# Power_Distribution.net
KiCad netlist of a schematic drawn in Altium Designer
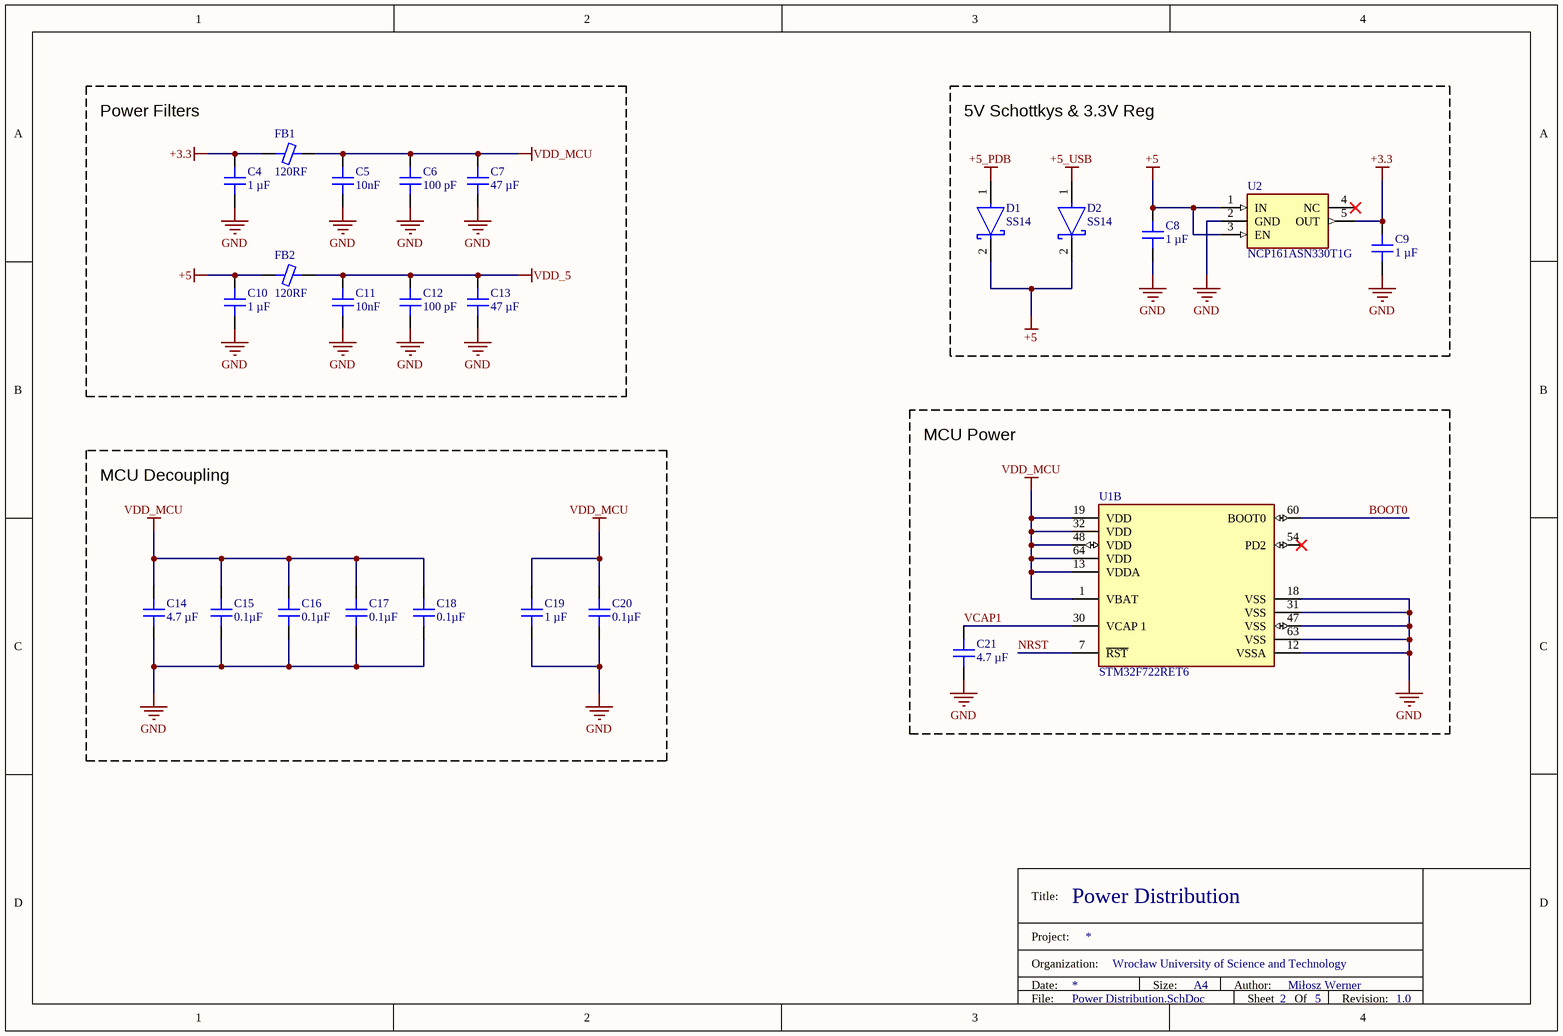
[diagram p0: Power Distribution.SchDoc]

(export (version "E")
  (design (tool "Eeschema 10.0.6"))
  (components
    (comp (ref "C4")
      (value "1 µF")
      (footprint "CAP 0603_1608")
      (description "CAP CER 1UF 25V X5R 0603")
      (fields
        (field (name "PART NUMBER") "CL10A105KA8NFNC")
        (field (name "MANUFACTURER") "Samsung Electro-Mechanics")
      )
      (libsource (lib "Celestial Altium Library - altium_library") (part "Capacitor"))
    )
    (comp (ref "C5")
      (value "10nF")
      (footprint "CAP 0603_1608")
      (description "CAP CER 10000PF 25V X7R 0603")
      (fields (field (name "PART NUMBER") "06033C103KAT2A") (field (name "MANUFACTURER") "AVX Corporation"))
      (libsource (lib "Celestial Altium Library - altium_library") (part "Capacitor"))
    )
    (comp (ref "C6")
      (value "100 pF")
      (footprint "CAP 0603_1608")
      (description "CAP CER 100PF 10V X7R 0603")
      (fields (field (name "PART NUMBER") "C0603C101K8RAC7867") (field (name "MANUFACTURER") "KEMET"))
      (libsource (lib "Celestial Altium Library - altium_library") (part "Capacitor"))
    )
    (comp (ref "C7")
      (value "47 µF")
      (footprint "CAP 0603_1608")
      (description "CAP CER 47UF 6.3V X5R 0603")
      (fields
        (field (name "PART NUMBER") "GRM188R60J476ME15D")
        (field (name "MANUFACTURER") "Murata Electronics")
      )
      (libsource (lib "Celestial Altium Library - altium_library") (part "Capacitor"))
    )
    (comp (ref "C8")
      (value "1 µF")
      (footprint "CAP 0603_1608")
      (description "CAP CER 1UF 25V X5R 0603")
      (fields
        (field (name "PART NUMBER") "CL10A105KA8NFNC")
        (field (name "MANUFACTURER") "Samsung Electro-Mechanics")
      )
      (libsource (lib "Celestial Altium Library - altium_library") (part "Capacitor"))
    )
    (comp (ref "C9")
      (value "1 µF")
      (footprint "CAP 0603_1608")
      (description "CAP CER 1UF 25V X5R 0603")
      (fields
        (field (name "PART NUMBER") "CL10A105KA8NFNC")
        (field (name "MANUFACTURER") "Samsung Electro-Mechanics")
      )
      (libsource (lib "Celestial Altium Library - altium_library") (part "Capacitor"))
    )
    (comp (ref "C10")
      (value "1 µF")
      (footprint "CAP 0603_1608")
      (description "CAP CER 1UF 25V X5R 0603")
      (fields
        (field (name "PART NUMBER") "CL10A105KA8NFNC")
        (field (name "MANUFACTURER") "Samsung Electro-Mechanics")
      )
      (libsource (lib "Celestial Altium Library - altium_library") (part "Capacitor"))
    )
    (comp (ref "C11")
      (value "10nF")
      (footprint "CAP 0603_1608")
      (description "CAP CER 10000PF 25V X7R 0603")
      (fields (field (name "PART NUMBER") "06033C103KAT2A") (field (name "MANUFACTURER") "AVX Corporation"))
      (libsource (lib "Celestial Altium Library - altium_library") (part "Capacitor"))
    )
    (comp (ref "C12")
      (value "100 pF")
      (footprint "CAP 0603_1608")
      (description "CAP CER 100PF 10V X7R 0603")
      (fields (field (name "PART NUMBER") "C0603C101K8RAC7867") (field (name "MANUFACTURER") "KEMET"))
      (libsource (lib "Celestial Altium Library - altium_library") (part "Capacitor"))
    )
    (comp (ref "C13")
      (value "47 µF")
      (footprint "CAP 0603_1608")
      (description "CAP CER 47UF 6.3V X5R 0603")
      (fields
        (field (name "PART NUMBER") "GRM188R60J476ME15D")
        (field (name "MANUFACTURER") "Murata Electronics")
      )
      (libsource (lib "Celestial Altium Library - altium_library") (part "Capacitor"))
    )
    (comp (ref "C14")
      (value "4.7 µF")
      (footprint "CAP 0603_1608")
      (description "CAP CER 4.7UF 25V X5R 0603")
      (fields
        (field (name "PART NUMBER") "GRM188R61E475KE11D")
        (field (name "MANUFACTURER") "Murata Electronics")
      )
      (libsource (lib "Celestial Altium Library - altium_library") (part "Capacitor"))
    )
    (comp (ref "C15")
      (value "0.1µF")
      (footprint "CAP 0603_1608")
      (description "CAP CER 0.1UF 25V X7R 0603")
      (fields (field (name "PART NUMBER") "06033C104JAT4A") (field (name "MANUFACTURER") "AVX Corporation"))
      (libsource (lib "Celestial Altium Library - altium_library") (part "Capacitor"))
    )
    (comp (ref "C16")
      (value "0.1µF")
      (footprint "CAP 0603_1608")
      (description "CAP CER 0.1UF 25V X7R 0603")
      (fields (field (name "PART NUMBER") "06033C104JAT4A") (field (name "MANUFACTURER") "AVX Corporation"))
      (libsource (lib "Celestial Altium Library - altium_library") (part "Capacitor"))
    )
    (comp (ref "C17")
      (value "0.1µF")
      (footprint "CAP 0603_1608")
      (description "CAP CER 0.1UF 25V X7R 0603")
      (fields (field (name "PART NUMBER") "06033C104JAT4A") (field (name "MANUFACTURER") "AVX Corporation"))
      (libsource (lib "Celestial Altium Library - altium_library") (part "Capacitor"))
    )
    (comp (ref "C18")
      (value "0.1µF")
      (footprint "CAP 0603_1608")
      (description "CAP CER 0.1UF 25V X7R 0603")
      (fields (field (name "PART NUMBER") "06033C104JAT4A") (field (name "MANUFACTURER") "AVX Corporation"))
      (libsource (lib "Celestial Altium Library - altium_library") (part "Capacitor"))
    )
    (comp (ref "C19")
      (value "1 µF")
      (footprint "CAP 0603_1608")
      (description "CAP CER 1UF 25V X5R 0603")
      (fields
        (field (name "PART NUMBER") "CL10A105KA8NFNC")
        (field (name "MANUFACTURER") "Samsung Electro-Mechanics")
      )
      (libsource (lib "Celestial Altium Library - altium_library") (part "Capacitor"))
    )
    (comp (ref "C20")
      (value "0.1µF")
      (footprint "CAP 0603_1608")
      (description "CAP CER 0.1UF 25V X7R 0603")
      (fields (field (name "PART NUMBER") "06033C104JAT4A") (field (name "MANUFACTURER") "AVX Corporation"))
      (libsource (lib "Celestial Altium Library - altium_library") (part "Capacitor"))
    )
    (comp (ref "C21")
      (value "4.7 µF")
      (footprint "CAP 0603_1608")
      (description "CAP CER 4.7UF 25V X5R 0603")
      (fields
        (field (name "PART NUMBER") "GRM188R61E475KE11D")
        (field (name "MANUFACTURER") "Murata Electronics")
      )
      (libsource (lib "Celestial Altium Library - altium_library") (part "Capacitor"))
    )
    (comp (ref "D1")
      (value "SS14")
      (footprint "FP-403AE-MFG")
      (description "DIODE SCHOTTKY 40V 1A SMA")
      (fields
        (field (name "MANUFACTURER") "ON Semiconductor")
        (field (name "OCTOPART") "https://octopart.com/ss14-on+semiconductor-29205033")
      )
      (libsource (lib "Altium Content Vault") (part "360ad2f4ac25a952324d13796385471"))
    )
    (comp (ref "D2")
      (value "SS14")
      (footprint "FP-403AE-MFG")
      (description "DIODE SCHOTTKY 40V 1A SMA")
      (fields
        (field (name "MANUFACTURER") "ON Semiconductor")
        (field (name "OCTOPART") "https://octopart.com/ss14-on+semiconductor-29205033")
      )
      (libsource (lib "Altium Content Vault") (part "360ad2f4ac25a952324d13796385471"))
    )
    (comp (ref "FB1")
      (value "120RF")
      (footprint "FER 0603_1608")
      (description "FERRITE BEAD 120 OHM 0603 1LN")
      (fields
        (field (name "PART NUMBER") "BLM18PG121SN1D")
        (field (name "MANUFACTURER") "Murata Electronics")
      )
      (libsource (lib "Celestial Altium Library - altium_library") (part "Ferrite Chip"))
    )
    (comp (ref "FB2")
      (value "120RF")
      (footprint "FER 0603_1608")
      (description "FERRITE BEAD 120 OHM 0603 1LN")
      (fields
        (field (name "PART NUMBER") "BLM18PG121SN1D")
        (field (name "MANUFACTURER") "Murata Electronics")
      )
      (libsource (lib "Celestial Altium Library - altium_library") (part "Ferrite Chip"))
    )
    (comp (ref "U1")
      (value "STM32F722RET6")
      (footprint "FP-LQFP64-5W-IPC_A")
      (description "IC MCU 32BIT 512KB FLASH 64LQFP")
      (libsource (lib "Altium Content Vault") (part "413d838e29415566e97646d24ea8a00"))
    )
    (comp (ref "U2")
      (value "NCP161ASN330T1G")
      (footprint "SamacSys:SOT95P280X145-5N")
      (description "Power Supply")
      (fields (field (name "MOUSER PART NUMBER") "863-NCP161ASN330T1G"))
      (libsource (lib "*") (part "NCP161ASN330T1G"))
    )
  )
  (nets
    (net (code "1") (name "+3.3") (class "Default")
      (node (ref "C4") (pin "2") (pinfunction "2_2") (pintype "passive"))
      (node (ref "C9") (pin "2") (pinfunction "2_2") (pintype "passive"))
      (node (ref "FB1") (pin "1") (pinfunction "1_1") (pintype "passive"))
      (node (ref "U2") (pin "5") (pinfunction "OUT_5") (pintype "output"))
    )
    (net (code "2") (name "+5") (class "Default")
      (node (ref "C10") (pin "2") (pinfunction "2_2") (pintype "passive"))
      (node (ref "C8") (pin "2") (pinfunction "2_2") (pintype "passive"))
      (node (ref "D1") (pin "2") (pinfunction "C_2") (pintype "passive"))
      (node (ref "D2") (pin "2") (pinfunction "C_2") (pintype "passive"))
      (node (ref "FB2") (pin "1") (pinfunction "1_1") (pintype "passive"))
      (node (ref "U2") (pin "1") (pinfunction "IN_1") (pintype "input"))
      (node (ref "U2") (pin "3") (pinfunction "EN_3") (pintype "input"))
    )
    (net (code "3") (name "+5_PDB") (class "Default")
      (node (ref "D1") (pin "1") (pinfunction "A_1") (pintype "passive"))
    )
    (net (code "4") (name "+5_USB") (class "Default")
      (node (ref "D2") (pin "1") (pinfunction "A_1") (pintype "passive"))
    )
    (net (code "5") (name "/BOOT0") (class "Default")
      (node (ref "U1") (pin "60") (pinfunction "BOOT0_60") (pintype "bidirectional"))
    )
    (net (code "6") (name "/NRST") (class "Default")
      (node (ref "U1") (pin "7") (pinfunction "~{RST}_7") (pintype "passive"))
    )
    (net (code "7") (name "/VCAP1") (class "Default")
      (node (ref "C21") (pin "2") (pinfunction "2_2") (pintype "passive"))
      (node (ref "U1") (pin "30") (pinfunction "VCAP_1_30") (pintype "passive"))
    )
    (net (code "8") (name "GND") (class "Default")
      (node (ref "C10") (pin "1") (pinfunction "1_1") (pintype "passive"))
      (node (ref "C11") (pin "1") (pinfunction "1_1") (pintype "passive"))
      (node (ref "C12") (pin "1") (pinfunction "1_1") (pintype "passive"))
      (node (ref "C13") (pin "1") (pinfunction "1_1") (pintype "passive"))
      (node (ref "C14") (pin "1") (pinfunction "1_1") (pintype "passive"))
      (node (ref "C15") (pin "1") (pinfunction "1_1") (pintype "passive"))
      (node (ref "C16") (pin "1") (pinfunction "1_1") (pintype "passive"))
      (node (ref "C17") (pin "1") (pinfunction "1_1") (pintype "passive"))
      (node (ref "C18") (pin "1") (pinfunction "1_1") (pintype "passive"))
      (node (ref "C19") (pin "1") (pinfunction "1_1") (pintype "passive"))
      (node (ref "C20") (pin "1") (pinfunction "1_1") (pintype "passive"))
      (node (ref "C21") (pin "1") (pinfunction "1_1") (pintype "passive"))
      (node (ref "C4") (pin "1") (pinfunction "1_1") (pintype "passive"))
      (node (ref "C5") (pin "1") (pinfunction "1_1") (pintype "passive"))
      (node (ref "C6") (pin "1") (pinfunction "1_1") (pintype "passive"))
      (node (ref "C7") (pin "1") (pinfunction "1_1") (pintype "passive"))
      (node (ref "C8") (pin "1") (pinfunction "1_1") (pintype "passive"))
      (node (ref "C9") (pin "1") (pinfunction "1_1") (pintype "passive"))
      (node (ref "U1") (pin "12") (pinfunction "VSSA_12") (pintype "passive"))
      (node (ref "U1") (pin "18") (pinfunction "VSS_18") (pintype "passive"))
      (node (ref "U1") (pin "31") (pinfunction "VSS_31") (pintype "passive"))
      (node (ref "U1") (pin "47") (pinfunction "VSS_47") (pintype "bidirectional"))
      (node (ref "U1") (pin "63") (pinfunction "VSS_63") (pintype "power_in"))
      (node (ref "U2") (pin "2") (pinfunction "GND_2") (pintype "power_in"))
    )
    (net (code "9") (name "VDD_5") (class "Default")
      (node (ref "C11") (pin "2") (pinfunction "2_2") (pintype "passive"))
      (node (ref "C12") (pin "2") (pinfunction "2_2") (pintype "passive"))
      (node (ref "C13") (pin "2") (pinfunction "2_2") (pintype "passive"))
      (node (ref "FB2") (pin "2") (pinfunction "2_2") (pintype "passive"))
    )
    (net (code "10") (name "VDD_MCU") (class "Default")
      (node (ref "C14") (pin "2") (pinfunction "2_2") (pintype "passive"))
      (node (ref "C15") (pin "2") (pinfunction "2_2") (pintype "passive"))
      (node (ref "C16") (pin "2") (pinfunction "2_2") (pintype "passive"))
      (node (ref "C17") (pin "2") (pinfunction "2_2") (pintype "passive"))
      (node (ref "C18") (pin "2") (pinfunction "2_2") (pintype "passive"))
      (node (ref "C19") (pin "2") (pinfunction "2_2") (pintype "passive"))
      (node (ref "C20") (pin "2") (pinfunction "2_2") (pintype "passive"))
      (node (ref "C5") (pin "2") (pinfunction "2_2") (pintype "passive"))
      (node (ref "C6") (pin "2") (pinfunction "2_2") (pintype "passive"))
      (node (ref "C7") (pin "2") (pinfunction "2_2") (pintype "passive"))
      (node (ref "FB1") (pin "2") (pinfunction "2_2") (pintype "passive"))
      (node (ref "U1") (pin "1") (pinfunction "VBAT_1") (pintype "passive"))
      (node (ref "U1") (pin "13") (pinfunction "VDDA_13") (pintype "passive"))
      (node (ref "U1") (pin "19") (pinfunction "VDD_19") (pintype "passive"))
      (node (ref "U1") (pin "32") (pinfunction "VDD_32") (pintype "passive"))
      (node (ref "U1") (pin "48") (pinfunction "VDD_48") (pintype "bidirectional"))
      (node (ref "U1") (pin "64") (pinfunction "VDD_64") (pintype "power_in"))
    )
    (net (code "11") (name "unconnected-(U1B-PD2-Pad54)") (class "Default")
      (node (ref "U1") (pin "54") (pinfunction "PD2_54") (pintype "bidirectional+no_connect"))
    )
    (net (code "12") (name "unconnected-(U2-NC-Pad4)") (class "Default")
      (node (ref "U2") (pin "4") (pinfunction "NC_4") (pintype "passive+no_connect"))
    )
  )
)
